# pca20054_sheet5_connectors.net
KiCad netlist of a schematic drawn in Altium Designer
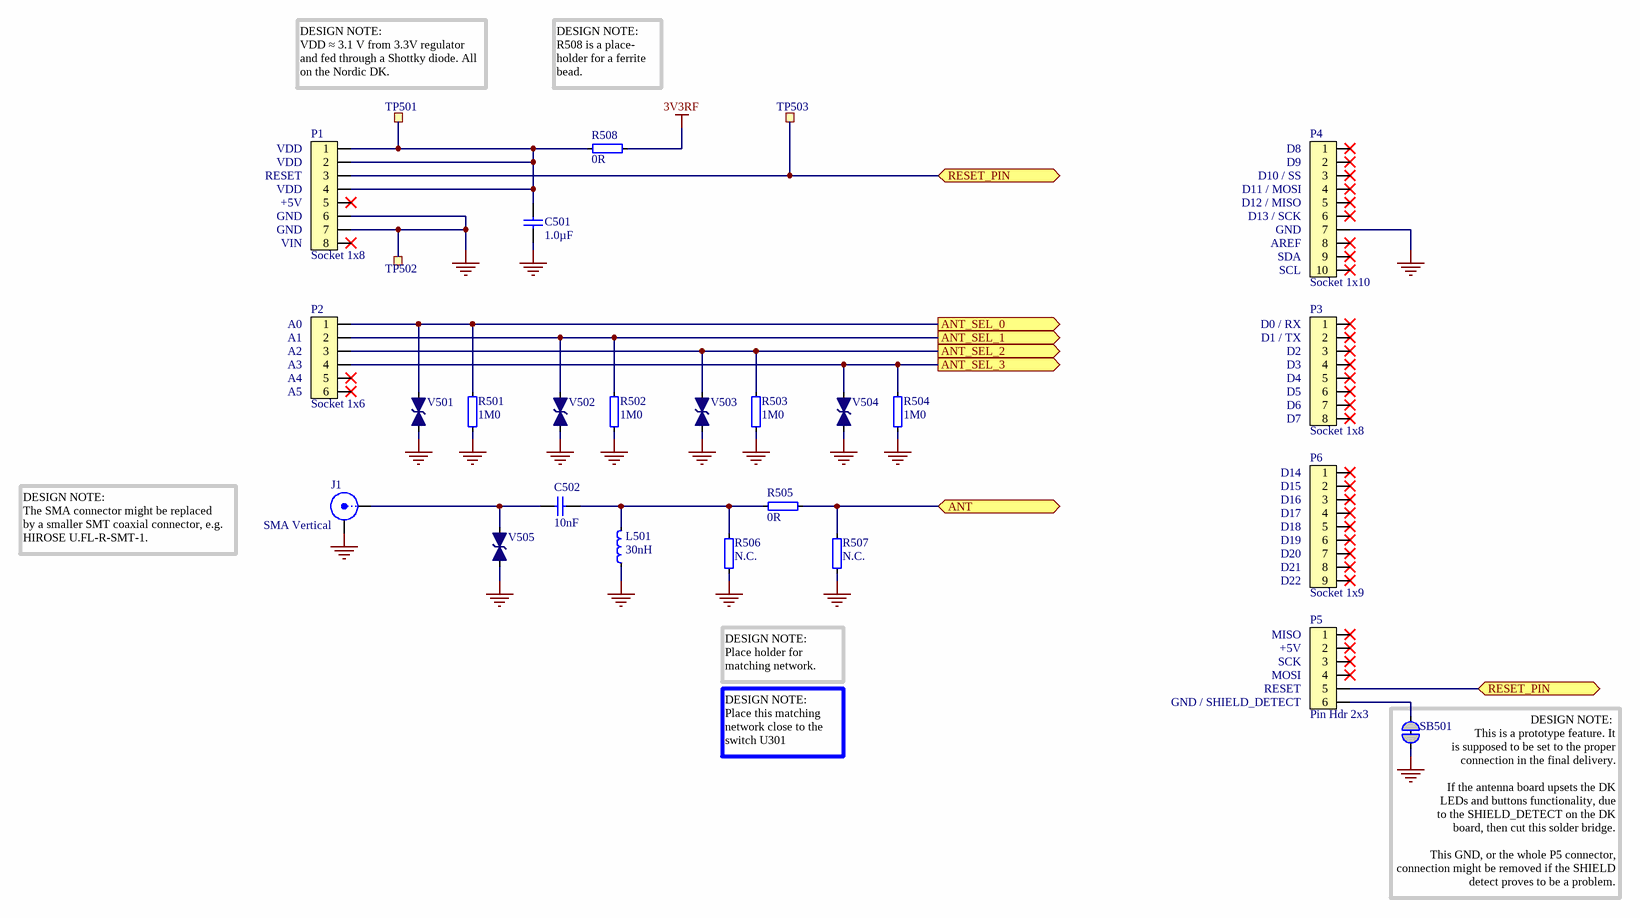
[diagram p0: pca20054_sheet5_connectors.SchDoc]

(export (version "E")
  (design (tool "Eeschema 10.0.6"))
  (components
    (comp (ref "C501")
      (value "1.0µF")
      (footprint "CAPC1608X06L")
      (description "Capacitor, X7R, ±10%")
      (fields (field (name "PART NUMBER") "C0603-1µ0") (field (name "PUBLISHER") "Nordic Semiconductor"))
      (libsource (lib "Nordic Passive DB") (part "CAP"))
    )
    (comp (ref "C502")
      (value "10nF")
      (footprint "CAPC1005X04L")
      (description "Capacitor, X7R, ±10%")
      (fields (field (name "PART NUMBER") "C0402-10n") (field (name "PUBLISHER") "Nordic Semiconductor"))
      (libsource (lib "Nordic Passive DB") (part "CAP"))
    )
    (comp (ref "J1")
      (value "SMA Vertical")
      (footprint "CON_SMA_COAX_FEM_STRAIGHT_5P_1")
      (description "SMA Vertical connector")
      (fields
        (field (name "PART NUMBER") "SMA-Vert-Std_Sigma")
        (field (name "PUBLISHER") "Nordic Semiconductor")
      )
      (libsource (lib "Nordic Passive DB") (part "SMA"))
    )
    (comp (ref "L501")
      (value "30nH")
      (footprint "INDC1005X04L_WW")
      (description "Inductor, 270mA, ±2%, 580mΩ, Q=25")
      (fields
        (field (name "PART NUMBER") "L0402-30n-Wirewound-Murata")
        (field (name "MANUFACTURER") "Murata")
        (field (name "PUBLISHER") "Nordic Semiconductor")
      )
      (libsource (lib "Nordic Passive DB") (part "IND"))
    )
    (comp (ref "P1")
      (value "Socket 1x8")
      (footprint "SOCKET_1x8_SMD")
      (description "Socket 1x8, 2.54mm (100mil), SMD")
      (fields
        (field (name "PART NUMBER") "Socket 1x8 SMD")
        (field (name "MANUFACTURER") "W-CON")
        (field (name "PUBLISHER") "Nordic Semiconductor")
      )
      (libsource (lib "Nordic Passive DB") (part "CONN-8"))
    )
    (comp (ref "P2")
      (value "Socket 1x6")
      (footprint "SOCKET_1x6_SMD")
      (description "Socket 1x6, 2.54mm (100mil), SMD")
      (fields
        (field (name "PART NUMBER") "Socket 1x6 SMD")
        (field (name "MANUFACTURER") "W-CON")
        (field (name "PUBLISHER") "Nordic Semiconductor")
      )
      (libsource (lib "Nordic Passive DB") (part "CONN-6"))
    )
    (comp (ref "P3")
      (value "Socket 1x8")
      (footprint "SOCKET_1x8_SMD")
      (description "Socket 1x8, 2.54mm (100mil), SMD")
      (fields
        (field (name "PART NUMBER") "Socket 1x8 SMD")
        (field (name "MANUFACTURER") "W-CON")
        (field (name "PUBLISHER") "Nordic Semiconductor")
      )
      (libsource (lib "Nordic Passive DB") (part "CONN-8"))
    )
    (comp (ref "P4")
      (value "Socket 1x10")
      (footprint "SOCKET_1x10_SMD")
      (description "Socket 1x10, 2.54mm (100mil), SMD")
      (fields
        (field (name "PART NUMBER") "Socket 1x10 SMD")
        (field (name "MANUFACTURER") "W-CON")
        (field (name "PUBLISHER") "Nordic Semiconductor")
      )
      (libsource (lib "Nordic Passive DB") (part "CONN-10"))
    )
    (comp (ref "P5")
      (value "Pin Hdr 2x3")
      (footprint "HDR_2x3-SMD")
      (description "Pin Header 2x3, 2.54mm (100mil) SMD")
      (fields
        (field (name "PART NUMBER") "Pin Header 2x3 SMD")
        (field (name "MANUFACTURER") "W-CON")
        (field (name "PUBLISHER") "Nordic Semiconductor")
      )
      (libsource (lib "Nordic Passive DB") (part "CONN-6"))
    )
    (comp (ref "P6")
      (value "Socket 1x9")
      (footprint "SOCKET_1x9_SMD")
      (description "Socket 1x9, 2.54mm (100mil), SMD")
      (fields
        (field (name "PART NUMBER") "Socket 1x9 SMD")
        (field (name "MANUFACTURER") "W-CON")
        (field (name "PUBLISHER") "Nordic Semiconductor")
      )
      (libsource (lib "Nordic Passive DB") (part "CONN-9"))
    )
    (comp (ref "R501")
      (value "1M0")
      (footprint "RESC1005X04L")
      (description "Resistor, ±1%, 0.063W")
      (fields (field (name "PART NUMBER") "R0402-1M0") (field (name "PUBLISHER") "Nordic Semiconductor"))
      (libsource (lib "Nordic Passive DB") (part "RES"))
    )
    (comp (ref "R502")
      (value "1M0")
      (footprint "RESC1005X04L")
      (description "Resistor, ±1%, 0.063W")
      (fields (field (name "PART NUMBER") "R0402-1M0") (field (name "PUBLISHER") "Nordic Semiconductor"))
      (libsource (lib "Nordic Passive DB") (part "RES"))
    )
    (comp (ref "R503")
      (value "1M0")
      (footprint "RESC1005X04L")
      (description "Resistor, ±1%, 0.063W")
      (fields (field (name "PART NUMBER") "R0402-1M0") (field (name "PUBLISHER") "Nordic Semiconductor"))
      (libsource (lib "Nordic Passive DB") (part "RES"))
    )
    (comp (ref "R504")
      (value "1M0")
      (footprint "RESC1005X04L")
      (description "Resistor, ±1%, 0.063W")
      (fields (field (name "PART NUMBER") "R0402-1M0") (field (name "PUBLISHER") "Nordic Semiconductor"))
      (libsource (lib "Nordic Passive DB") (part "RES"))
    )
    (comp (ref "R505")
      (value "0R")
      (footprint "RESC1005X04L")
      (description "Resistor, ±5%, 0.063W")
      (fields (field (name "PART NUMBER") "R0402-0R") (field (name "PUBLISHER") "Nordic Semiconductor"))
      (libsource (lib "Nordic Passive DB") (part "RES"))
    )
    (comp (ref "R506")
      (value "N.C.")
      (footprint "RESC1005X04L_NC")
      (description "Not mounted")
      (fields (field (name "PART NUMBER") "R0402-N.C.") (field (name "PUBLISHER") "Nordic Semiconductor"))
      (libsource (lib "Nordic Passive DB") (part "RES"))
    )
    (comp (ref "R507")
      (value "N.C.")
      (footprint "RESC1005X04L_NC")
      (description "Not mounted")
      (fields (field (name "PART NUMBER") "R0402-N.C.") (field (name "PUBLISHER") "Nordic Semiconductor"))
      (libsource (lib "Nordic Passive DB") (part "RES"))
    )
    (comp (ref "R508")
      (value "0R")
      (footprint "RESC1005X04L")
      (description "Resistor, ±5%, 0.063W")
      (fields (field (name "PART NUMBER") "R0402-0R") (field (name "PUBLISHER") "Nordic Semiconductor"))
      (libsource (lib "Nordic Passive DB") (part "RES"))
    )
    (comp (ref "SB501")
      (value "Solderbridge")
      (footprint "Solderbridge_Shorted_Power")
      (description "Shorted Solderbridge Power")
      (fields
        (field (name "PART NUMBER") "Solderbridge Shorted Power")
        (field (name "PUBLISHER") "Nordic Semiconductor")
      )
      (libsource (lib "Nordic Passive DB") (part "SOLDERBRIDGE_SHORTED"))
    )
    (comp (ref "TP501")
      (value "Ø1.0mm,SMD")
      (footprint "TP_SMD_Ø1.0mm")
      (description "1.0mm circular SMD testpad")
      (fields
        (field (name "PART NUMBER") "TP_SMD_Ø1.0MM")
        (field (name "MANUFACTURER") "Nordic Semiconductor")
        (field (name "PUBLISHER") "Nordic Semiconductor")
      )
      (libsource (lib "Nordic Passive DB") (part "TESTPAD"))
    )
    (comp (ref "TP502")
      (value "Ø1.0mm,SMD")
      (footprint "TP_SMD_Ø1.0mm")
      (description "1.0mm circular SMD testpad")
      (fields
        (field (name "PART NUMBER") "TP_SMD_Ø1.0MM")
        (field (name "MANUFACTURER") "Nordic Semiconductor")
        (field (name "PUBLISHER") "Nordic Semiconductor")
      )
      (libsource (lib "") (part "TESTPAD_1"))
    )
    (comp (ref "TP503")
      (value "Ø1.0mm,SMD")
      (footprint "TP_SMD_Ø1.0mm")
      (description "1.0mm circular SMD testpad")
      (fields
        (field (name "PART NUMBER") "TP_SMD_Ø1.0MM")
        (field (name "MANUFACTURER") "Nordic Semiconductor")
        (field (name "PUBLISHER") "Nordic Semiconductor")
      )
      (libsource (lib "Nordic Passive DB") (part "TESTPAD"))
    )
    (comp (ref "V501")
      (value "LXES15AAA1-133")
      (footprint "RESC1005X04L")
      (description "TVS DIODE 15VWM 0402")
      (fields (field (name "MANUFACTURER") "Murata") (field (name "PUBLISHER") "Nordic Semiconductor"))
      (libsource (lib "Nordic Discrete DB") (part "D{colon}SUPP"))
    )
    (comp (ref "V502")
      (value "LXES15AAA1-133")
      (footprint "RESC1005X04L")
      (description "TVS DIODE 15VWM 0402")
      (fields (field (name "MANUFACTURER") "Murata") (field (name "PUBLISHER") "Nordic Semiconductor"))
      (libsource (lib "Nordic Discrete DB") (part "D{colon}SUPP"))
    )
    (comp (ref "V503")
      (value "LXES15AAA1-133")
      (footprint "RESC1005X04L")
      (description "TVS DIODE 15VWM 0402")
      (fields (field (name "MANUFACTURER") "Murata") (field (name "PUBLISHER") "Nordic Semiconductor"))
      (libsource (lib "Nordic Discrete DB") (part "D{colon}SUPP"))
    )
    (comp (ref "V504")
      (value "LXES15AAA1-133")
      (footprint "RESC1005X04L")
      (description "TVS DIODE 15VWM 0402")
      (fields (field (name "MANUFACTURER") "Murata") (field (name "PUBLISHER") "Nordic Semiconductor"))
      (libsource (lib "Nordic Discrete DB") (part "D{colon}SUPP"))
    )
    (comp (ref "V505")
      (value "LXES15AAA1-133")
      (footprint "RESC1005X04L")
      (description "TVS DIODE 15VWM 0402")
      (fields (field (name "MANUFACTURER") "Murata") (field (name "PUBLISHER") "Nordic Semiconductor"))
      (libsource (lib "Nordic Discrete DB") (part "D{colon}SUPP"))
    )
  )
  (nets
    (net (code "1") (name "/ANT") (class "Default")
      (node (ref "R505") (pin "2") (pinfunction "2_2") (pintype "passive"))
      (node (ref "R507") (pin "2") (pinfunction "2_2") (pintype "passive"))
    )
    (net (code "2") (name "/ANT_SEL_0") (class "Default")
      (node (ref "P2") (pin "1") (pinfunction "1_1") (pintype "passive"))
      (node (ref "R501") (pin "2") (pinfunction "2_2") (pintype "passive"))
      (node (ref "V501") (pin "1") (pintype "passive"))
    )
    (net (code "3") (name "/ANT_SEL_1") (class "Default")
      (node (ref "P2") (pin "2") (pinfunction "2_2") (pintype "passive"))
      (node (ref "R502") (pin "2") (pinfunction "2_2") (pintype "passive"))
      (node (ref "V502") (pin "1") (pintype "passive"))
    )
    (net (code "4") (name "/ANT_SEL_2") (class "Default")
      (node (ref "P2") (pin "3") (pinfunction "3_3") (pintype "passive"))
      (node (ref "R503") (pin "2") (pinfunction "2_2") (pintype "passive"))
      (node (ref "V503") (pin "1") (pintype "passive"))
    )
    (net (code "5") (name "/ANT_SEL_3") (class "Default")
      (node (ref "P2") (pin "4") (pinfunction "4_4") (pintype "passive"))
      (node (ref "R504") (pin "2") (pinfunction "2_2") (pintype "passive"))
      (node (ref "V504") (pin "1") (pintype "passive"))
    )
    (net (code "6") (name "/RESET_PIN") (class "Default")
      (node (ref "P1") (pin "3") (pinfunction "3_3") (pintype "passive"))
      (node (ref "P5") (pin "5") (pinfunction "5_5") (pintype "passive"))
      (node (ref "TP503") (pin "1") (pinfunction "1_1") (pintype "passive"))
    )
    (net (code "7") (name "3V3RF") (class "Default")
      (node (ref "R508") (pin "2") (pinfunction "2_2") (pintype "passive"))
    )
    (net (code "8") (name "GND") (class "Default")
      (node (ref "C501") (pin "1") (pinfunction "1_1") (pintype "passive"))
      (node (ref "J1") (pin "2") (pinfunction "Y_2") (pintype "passive"))
      (node (ref "L501") (pin "1") (pinfunction "1_1") (pintype "passive"))
      (node (ref "P1") (pin "6") (pinfunction "6_6") (pintype "passive"))
      (node (ref "P1") (pin "7") (pinfunction "7_7") (pintype "passive"))
      (node (ref "P4") (pin "7") (pinfunction "7_7") (pintype "passive"))
      (node (ref "R501") (pin "1") (pinfunction "1_1") (pintype "passive"))
      (node (ref "R502") (pin "1") (pinfunction "1_1") (pintype "passive"))
      (node (ref "R503") (pin "1") (pinfunction "1_1") (pintype "passive"))
      (node (ref "R504") (pin "1") (pinfunction "1_1") (pintype "passive"))
      (node (ref "R506") (pin "1") (pinfunction "1_1") (pintype "passive"))
      (node (ref "R507") (pin "1") (pinfunction "1_1") (pintype "passive"))
      (node (ref "SB501") (pin "2") (pinfunction "1_2") (pintype "passive"))
      (node (ref "TP502") (pin "1") (pinfunction "1_1") (pintype "passive"))
      (node (ref "V501") (pin "2") (pintype "passive"))
      (node (ref "V502") (pin "2") (pintype "passive"))
      (node (ref "V503") (pin "2") (pintype "passive"))
      (node (ref "V504") (pin "2") (pintype "passive"))
      (node (ref "V505") (pin "2") (pintype "passive"))
    )
    (net (code "9") (name "Net-(C501-Pad2)") (class "Default")
      (node (ref "C501") (pin "2") (pinfunction "2_2") (pintype "passive"))
      (node (ref "P1") (pin "1") (pinfunction "1_1") (pintype "passive"))
      (node (ref "P1") (pin "2") (pinfunction "2_2") (pintype "passive"))
      (node (ref "P1") (pin "4") (pinfunction "4_4") (pintype "passive"))
      (node (ref "R508") (pin "1") (pinfunction "1_1") (pintype "passive"))
      (node (ref "TP501") (pin "1") (pinfunction "1_1") (pintype "passive"))
    )
    (net (code "10") (name "Net-(C502-Pad1)") (class "Default")
      (node (ref "C502") (pin "1") (pinfunction "1_1") (pintype "passive"))
      (node (ref "L501") (pin "2") (pinfunction "2_2") (pintype "passive"))
      (node (ref "R505") (pin "1") (pinfunction "1_1") (pintype "passive"))
      (node (ref "R506") (pin "2") (pinfunction "2_2") (pintype "passive"))
    )
    (net (code "11") (name "Net-(J1-X)") (class "Default")
      (node (ref "C502") (pin "2") (pinfunction "2_2") (pintype "passive"))
      (node (ref "J1") (pin "1") (pinfunction "X_1") (pintype "passive"))
      (node (ref "V505") (pin "1") (pintype "passive"))
    )
    (net (code "12") (name "Net-(SB501-0)") (class "Default")
      (node (ref "P5") (pin "6") (pinfunction "6_6") (pintype "passive"))
      (node (ref "SB501") (pin "1") (pinfunction "0_1") (pintype "passive"))
    )
    (net (code "13") (name "unconnected-(P1-Pad5)") (class "Default")
      (node (ref "P1") (pin "5") (pinfunction "5_5") (pintype "passive+no_connect"))
    )
    (net (code "14") (name "unconnected-(P1-Pad8)") (class "Default")
      (node (ref "P1") (pin "8") (pinfunction "8_8") (pintype "passive+no_connect"))
    )
    (net (code "15") (name "unconnected-(P2-Pad5)") (class "Default")
      (node (ref "P2") (pin "5") (pinfunction "5_5") (pintype "passive+no_connect"))
    )
    (net (code "16") (name "unconnected-(P2-Pad6)") (class "Default")
      (node (ref "P2") (pin "6") (pinfunction "6_6") (pintype "passive+no_connect"))
    )
    (net (code "17") (name "unconnected-(P3-Pad1)") (class "Default")
      (node (ref "P3") (pin "1") (pinfunction "1_1") (pintype "passive+no_connect"))
    )
    (net (code "18") (name "unconnected-(P3-Pad2)") (class "Default")
      (node (ref "P3") (pin "2") (pinfunction "2_2") (pintype "passive+no_connect"))
    )
    (net (code "19") (name "unconnected-(P3-Pad3)") (class "Default")
      (node (ref "P3") (pin "3") (pinfunction "3_3") (pintype "passive+no_connect"))
    )
    (net (code "20") (name "unconnected-(P3-Pad4)") (class "Default")
      (node (ref "P3") (pin "4") (pinfunction "4_4") (pintype "passive+no_connect"))
    )
    (net (code "21") (name "unconnected-(P3-Pad5)") (class "Default")
      (node (ref "P3") (pin "5") (pinfunction "5_5") (pintype "passive+no_connect"))
    )
    (net (code "22") (name "unconnected-(P3-Pad6)") (class "Default")
      (node (ref "P3") (pin "6") (pinfunction "6_6") (pintype "passive+no_connect"))
    )
    (net (code "23") (name "unconnected-(P3-Pad7)") (class "Default")
      (node (ref "P3") (pin "7") (pinfunction "7_7") (pintype "passive+no_connect"))
    )
    (net (code "24") (name "unconnected-(P3-Pad8)") (class "Default")
      (node (ref "P3") (pin "8") (pinfunction "8_8") (pintype "passive+no_connect"))
    )
    (net (code "25") (name "unconnected-(P4-Pad1)") (class "Default")
      (node (ref "P4") (pin "1") (pinfunction "1_1") (pintype "passive+no_connect"))
    )
    (net (code "26") (name "unconnected-(P4-Pad2)") (class "Default")
      (node (ref "P4") (pin "2") (pinfunction "2_2") (pintype "passive+no_connect"))
    )
    (net (code "27") (name "unconnected-(P4-Pad3)") (class "Default")
      (node (ref "P4") (pin "3") (pinfunction "3_3") (pintype "passive+no_connect"))
    )
    (net (code "28") (name "unconnected-(P4-Pad4)") (class "Default")
      (node (ref "P4") (pin "4") (pinfunction "4_4") (pintype "passive+no_connect"))
    )
    (net (code "29") (name "unconnected-(P4-Pad5)") (class "Default")
      (node (ref "P4") (pin "5") (pinfunction "5_5") (pintype "passive+no_connect"))
    )
    (net (code "30") (name "unconnected-(P4-Pad6)") (class "Default")
      (node (ref "P4") (pin "6") (pinfunction "6_6") (pintype "passive+no_connect"))
    )
    (net (code "31") (name "unconnected-(P4-Pad8)") (class "Default")
      (node (ref "P4") (pin "8") (pinfunction "8_8") (pintype "passive+no_connect"))
    )
    (net (code "32") (name "unconnected-(P4-Pad9)") (class "Default")
      (node (ref "P4") (pin "9") (pinfunction "9_9") (pintype "passive+no_connect"))
    )
    (net (code "33") (name "unconnected-(P4-Pad10)") (class "Default")
      (node (ref "P4") (pin "10") (pinfunction "10_10") (pintype "passive+no_connect"))
    )
    (net (code "34") (name "unconnected-(P5-Pad1)") (class "Default")
      (node (ref "P5") (pin "1") (pinfunction "1_1") (pintype "passive+no_connect"))
    )
    (net (code "35") (name "unconnected-(P5-Pad2)") (class "Default")
      (node (ref "P5") (pin "2") (pinfunction "2_2") (pintype "passive+no_connect"))
    )
    (net (code "36") (name "unconnected-(P5-Pad3)") (class "Default")
      (node (ref "P5") (pin "3") (pinfunction "3_3") (pintype "passive+no_connect"))
    )
    (net (code "37") (name "unconnected-(P5-Pad4)") (class "Default")
      (node (ref "P5") (pin "4") (pinfunction "4_4") (pintype "passive+no_connect"))
    )
    (net (code "38") (name "unconnected-(P6-Pad1)") (class "Default")
      (node (ref "P6") (pin "1") (pinfunction "1_1") (pintype "passive+no_connect"))
    )
    (net (code "39") (name "unconnected-(P6-Pad2)") (class "Default")
      (node (ref "P6") (pin "2") (pinfunction "2_2") (pintype "passive+no_connect"))
    )
    (net (code "40") (name "unconnected-(P6-Pad3)") (class "Default")
      (node (ref "P6") (pin "3") (pinfunction "3_3") (pintype "passive+no_connect"))
    )
    (net (code "41") (name "unconnected-(P6-Pad4)") (class "Default")
      (node (ref "P6") (pin "4") (pinfunction "4_4") (pintype "passive+no_connect"))
    )
    (net (code "42") (name "unconnected-(P6-Pad5)") (class "Default")
      (node (ref "P6") (pin "5") (pinfunction "5_5") (pintype "passive+no_connect"))
    )
    (net (code "43") (name "unconnected-(P6-Pad6)") (class "Default")
      (node (ref "P6") (pin "6") (pinfunction "6_6") (pintype "passive+no_connect"))
    )
    (net (code "44") (name "unconnected-(P6-Pad7)") (class "Default")
      (node (ref "P6") (pin "7") (pinfunction "7_7") (pintype "passive+no_connect"))
    )
    (net (code "45") (name "unconnected-(P6-Pad8)") (class "Default")
      (node (ref "P6") (pin "8") (pinfunction "8_8") (pintype "passive+no_connect"))
    )
    (net (code "46") (name "unconnected-(P6-Pad9)") (class "Default")
      (node (ref "P6") (pin "9") (pinfunction "9_9") (pintype "passive+no_connect"))
    )
  )
)
